# pmu.net
KiCad netlist of a schematic drawn in Altium Designer
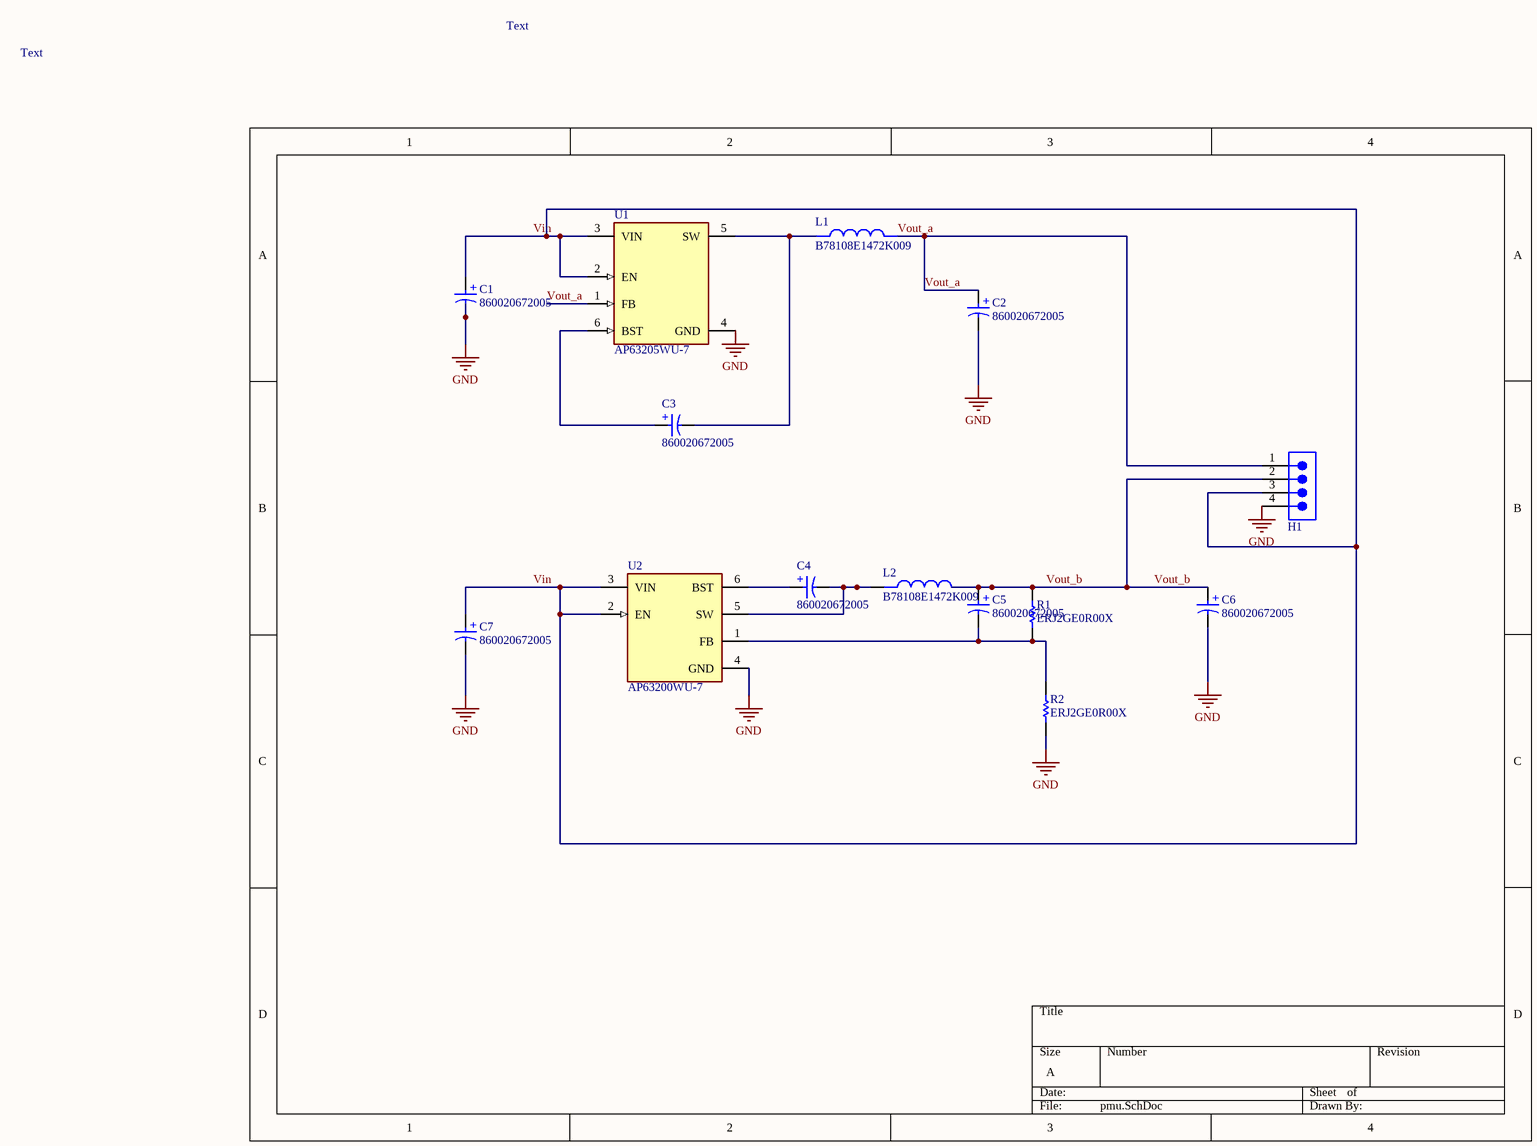
[diagram p0: pmu.SchDoc]

(export (version "E")
  (design (tool "Eeschema 10.0.6"))
  (components
    (comp (ref "C1")
      (value "860020672005")
      (footprint "WCAP-ATG5_D5H11")
      (description "860020672005 WCAP-ATG5 Aluminum Electrolytic Capacitors")
      (fields (field (name "TOLERANCE") "20%"))
      (libsource (lib "Altium Content Vault") (part "Capacitor_Polarized"))
    )
    (comp (ref "C2")
      (value "860020672005")
      (footprint "WCAP-ATG5_D5H11")
      (description "860020672005 WCAP-ATG5 Aluminum Electrolytic Capacitors")
      (fields (field (name "TOLERANCE") "20%"))
      (libsource (lib "Altium Content Vault") (part "Capacitor_Polarized"))
    )
    (comp (ref "C3")
      (value "860020672005")
      (footprint "WCAP-ATG5_D5H11")
      (description "860020672005 WCAP-ATG5 Aluminum Electrolytic Capacitors")
      (fields (field (name "TOLERANCE") "20%"))
      (libsource (lib "Altium Content Vault") (part "Capacitor_Polarized"))
    )
    (comp (ref "C4")
      (value "860020672005")
      (footprint "WCAP-ATG5_D5H11")
      (description "860020672005 WCAP-ATG5 Aluminum Electrolytic Capacitors")
      (fields (field (name "TOLERANCE") "20%"))
      (libsource (lib "Altium Content Vault") (part "Capacitor_Polarized"))
    )
    (comp (ref "C5")
      (value "860020672005")
      (footprint "WCAP-ATG5_D5H11")
      (description "860020672005 WCAP-ATG5 Aluminum Electrolytic Capacitors")
      (fields (field (name "TOLERANCE") "20%"))
      (libsource (lib "Altium Content Vault") (part "Capacitor_Polarized"))
    )
    (comp (ref "C6")
      (value "860020672005")
      (footprint "WCAP-ATG5_D5H11")
      (description "860020672005 WCAP-ATG5 Aluminum Electrolytic Capacitors")
      (fields (field (name "TOLERANCE") "20%"))
      (libsource (lib "Altium Content Vault") (part "Capacitor_Polarized"))
    )
    (comp (ref "C7")
      (value "860020672005")
      (footprint "WCAP-ATG5_D5H11")
      (description "860020672005 WCAP-ATG5 Aluminum Electrolytic Capacitors")
      (fields (field (name "TOLERANCE") "20%"))
      (libsource (lib "Altium Content Vault") (part "Capacitor_Polarized"))
    )
    (comp (ref "H1")
      (value "61300411121")
      (footprint "61300411121")
      (description "WR-PHD Pin Header, THT, Vertical, pitch 2.54mm, 1 Row, 4P")
      (fields (field (name "MANUFACTURER") "Wurth Elektronik"))
      (libsource (lib "pmu") (part "61300411121"))
    )
    (comp (ref "L1")
      (value "B78108E1472K009")
      (footprint "INDAD1430W80L950D400")
      (description "4.7 ÂµH Unshielded Drum Core, Wirewound Inductor 2.75 A 85mOhm Max Axial")
      (fields (field (name "DIGI-KEY_PART_NUMBER") "495-76025-1-ND") (field (name "MF") "EPCOS"))
      (libsource (lib "B78108E1472K009") (part "B78108E1472K009"))
    )
    (comp (ref "L2")
      (value "B78108E1472K009")
      (footprint "INDAD1430W80L950D400")
      (description "4.7 ÂµH Unshielded Drum Core, Wirewound Inductor 2.75 A 85mOhm Max Axial")
      (fields (field (name "DIGI-KEY_PART_NUMBER") "495-76025-1-ND") (field (name "MF") "EPCOS"))
      (libsource (lib "B78108E1472K009") (part "B78108E1472K009"))
    )
    (comp (ref "R1")
      (value "ERJ2GE0R00X")
      (footprint "RESC1005X40X25LL05T05")
      (description "Chip Resistor, 0 Ohm, 0.1 W, -55 to 155 degC, 0402 (1005 Metric), RoHS, Tape and Reel")
      (fields (field (name "MANUFACTURER") "Panasonic") (field (name "TOLERANCE") "5%"))
      (libsource (lib "Altium Content Vault") (part "RES-2"))
    )
    (comp (ref "R2")
      (value "ERJ2GE0R00X")
      (footprint "RESC1005X40X25LL05T05")
      (description "Chip Resistor, 0 Ohm, 0.1 W, -55 to 155 degC, 0402 (1005 Metric), RoHS, Tape and Reel")
      (fields (field (name "MANUFACTURER") "Panasonic") (field (name "TOLERANCE") "5%"))
      (libsource (lib "Altium Content Vault") (part "RES-2"))
    )
    (comp (ref "U1")
      (value "AP63205WU-7")
      (footprint "FP-TSOT26-MFG")
      (description "IC REG BUCK 5V 2A TSOT26")
      (fields
        (field (name "MANUFACTURER") "Diodes Inc.")
        (field (name "OCTOPART") "https://octopart.com/ap63205wu-7-diodes+inc.-98099551")
      )
      (libsource (lib "Altium Content Vault") (part "029bc9fbfa4a99dbb8b3a24c2adb655"))
    )
    (comp (ref "U2")
      (value "AP63200WU-7")
      (footprint "FP-TSOT26-MFG")
      (description "IC REG BUCK ADJUSTABLE 2A TSOT26")
      (fields
        (field (name "OCTOPART") "https://octopart.com/ap63200wu-7-diodes+inc.-98099548")
        (field (name "MANUFACTURER") "Diodes Inc.")
      )
      (libsource (lib "Altium Content Vault") (part "2ae3aed49e7ee94ca813948749813a1"))
    )
  )
  (nets
    (net (code "1") (name "/Vin") (class "Default")
      (node (ref "C1") (pin "1") (pinfunction "P_1") (pintype "passive"))
      (node (ref "C7") (pin "1") (pinfunction "P_1") (pintype "passive"))
      (node (ref "H1") (pin "3") (pinfunction "3_3") (pintype "passive"))
      (node (ref "U1") (pin "2") (pinfunction "EN_2") (pintype "input"))
      (node (ref "U1") (pin "3") (pinfunction "VIN_3") (pintype "power_in"))
      (node (ref "U2") (pin "2") (pinfunction "EN_2") (pintype "input"))
      (node (ref "U2") (pin "3") (pinfunction "VIN_3") (pintype "power_in"))
    )
    (net (code "2") (name "/Vout_a") (class "Default")
      (node (ref "C2") (pin "1") (pinfunction "P_1") (pintype "passive"))
      (node (ref "H1") (pin "1") (pinfunction "1_1") (pintype "passive"))
      (node (ref "L1") (pin "2") (pinfunction "2_2") (pintype "passive"))
      (node (ref "U1") (pin "1") (pinfunction "FB_1") (pintype "input"))
    )
    (net (code "3") (name "/Vout_b") (class "Default")
      (node (ref "C5") (pin "1") (pinfunction "P_1") (pintype "passive"))
      (node (ref "C6") (pin "1") (pinfunction "P_1") (pintype "passive"))
      (node (ref "H1") (pin "2") (pinfunction "2_2") (pintype "passive"))
      (node (ref "L2") (pin "2") (pinfunction "2_2") (pintype "passive"))
      (node (ref "R1") (pin "2") (pinfunction "2_2") (pintype "passive"))
    )
    (net (code "4") (name "GND") (class "Default")
      (node (ref "C1") (pin "2") (pinfunction "N_2") (pintype "passive"))
      (node (ref "C2") (pin "2") (pinfunction "N_2") (pintype "passive"))
      (node (ref "C6") (pin "2") (pinfunction "N_2") (pintype "passive"))
      (node (ref "C7") (pin "2") (pinfunction "N_2") (pintype "passive"))
      (node (ref "H1") (pin "4") (pinfunction "4_4") (pintype "passive"))
      (node (ref "R2") (pin "1") (pinfunction "1_1") (pintype "passive"))
      (node (ref "U1") (pin "4") (pinfunction "GND_4") (pintype "power_in"))
      (node (ref "U2") (pin "4") (pinfunction "GND_4") (pintype "power_in"))
    )
    (net (code "5") (name "Net-(C3-N)") (class "Default")
      (node (ref "C3") (pin "2") (pinfunction "N_2") (pintype "passive"))
      (node (ref "L1") (pin "1") (pinfunction "1_1") (pintype "passive"))
      (node (ref "U1") (pin "5") (pinfunction "SW_5") (pintype "power_in"))
    )
    (net (code "6") (name "Net-(C3-P)") (class "Default")
      (node (ref "C3") (pin "1") (pinfunction "P_1") (pintype "passive"))
      (node (ref "U1") (pin "6") (pinfunction "BST_6") (pintype "input"))
    )
    (net (code "7") (name "Net-(C4-N)") (class "Default")
      (node (ref "C4") (pin "2") (pinfunction "N_2") (pintype "passive"))
      (node (ref "L2") (pin "1") (pinfunction "1_1") (pintype "passive"))
      (node (ref "U2") (pin "5") (pinfunction "SW_5") (pintype "passive"))
    )
    (net (code "8") (name "Net-(C4-P)") (class "Default")
      (node (ref "C4") (pin "1") (pinfunction "P_1") (pintype "passive"))
      (node (ref "U2") (pin "6") (pinfunction "BST_6") (pintype "passive"))
    )
    (net (code "9") (name "Net-(C5-N)") (class "Default")
      (node (ref "C5") (pin "2") (pinfunction "N_2") (pintype "passive"))
      (node (ref "R1") (pin "1") (pinfunction "1_1") (pintype "passive"))
      (node (ref "R2") (pin "2") (pinfunction "2_2") (pintype "passive"))
      (node (ref "U2") (pin "1") (pinfunction "FB_1") (pintype "passive"))
    )
  )
)
